# internal_env_board_new.net
KiCad netlist of a schematic drawn in EAGLE
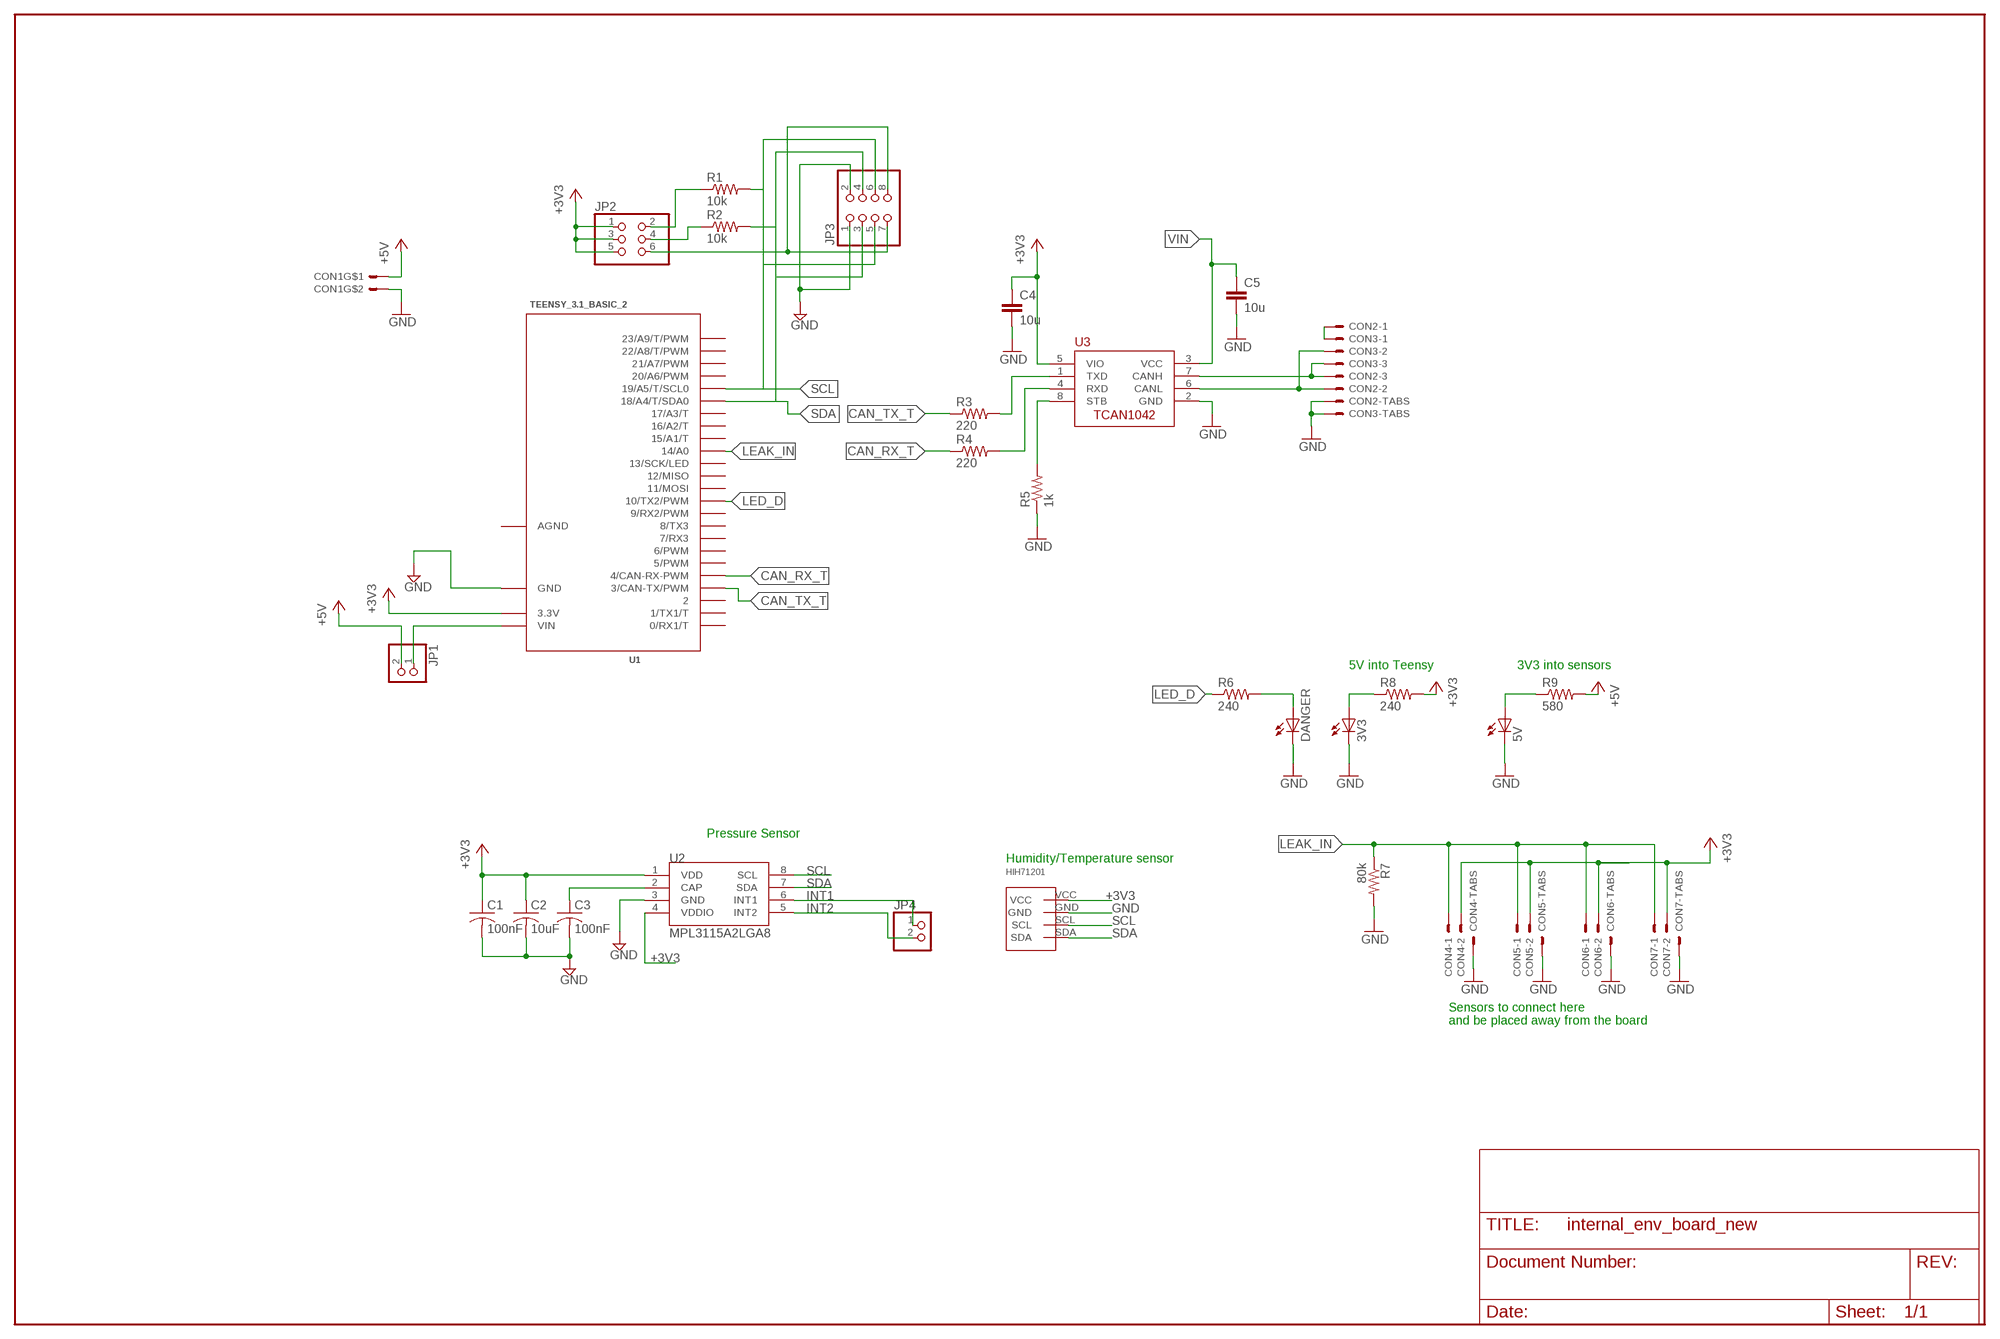
[diagram p0: schematic, sheet 1]

(export (version "E")
  (design (tool "Eeschema 10.0.6"))
  (components
    (comp (ref "3V3")
      (value "LEDSMT1206")
      (footprint "eagle-import:1206")
      (libsource (lib "eagle-import") (part "LEDSMT1206"))
    )
    (comp (ref "5V")
      (value "LEDSMT1206")
      (footprint "eagle-import:1206")
      (libsource (lib "eagle-import") (part "LEDSMT1206"))
    )
    (comp (ref "C1")
      (value "100nF")
      (footprint "eagle-import:C1206")
      (libsource (lib "eagle-import") (part "C-USC1206"))
    )
    (comp (ref "C2")
      (value "10uF")
      (footprint "eagle-import:C1206")
      (libsource (lib "eagle-import") (part "C-USC1206"))
    )
    (comp (ref "C3")
      (value "100nF")
      (footprint "eagle-import:C1206")
      (libsource (lib "eagle-import") (part "C-USC1206"))
    )
    (comp (ref "C4")
      (value "10u")
      (footprint "eagle-import:C0805")
      (libsource (lib "eagle-import") (part "C-EUC0805"))
    )
    (comp (ref "C5")
      (value "10u")
      (footprint "eagle-import:C0805")
      (libsource (lib "eagle-import") (part "C-EUC0805"))
    )
    (comp (ref "CON1")
      (value "MOLEX_5566-2")
      (footprint "eagle-import:5566-2")
      (libsource (lib "eagle-import") (part "MOLEX_5566-2"))
    )
    (comp (ref "CON2")
      (value "SM03B-GHS-TB")
      (footprint "eagle-import:SM03B-GHS-TB")
      (libsource (lib "eagle-import") (part "SM03B-GHS-TB"))
    )
    (comp (ref "CON3")
      (value "SM03B-GHS-TB")
      (footprint "eagle-import:SM03B-GHS-TB")
      (libsource (lib "eagle-import") (part "SM03B-GHS-TB"))
    )
    (comp (ref "CON4")
      (value "SM02B-GHS-TB")
      (footprint "eagle-import:SM02B-GHS-TB")
      (libsource (lib "eagle-import") (part "SM02B-GHS-TB"))
    )
    (comp (ref "CON5")
      (value "SM02B-GHS-TB")
      (footprint "eagle-import:SM02B-GHS-TB")
      (libsource (lib "eagle-import") (part "SM02B-GHS-TB"))
    )
    (comp (ref "CON6")
      (value "SM02B-GHS-TB")
      (footprint "eagle-import:SM02B-GHS-TB")
      (libsource (lib "eagle-import") (part "SM02B-GHS-TB"))
    )
    (comp (ref "CON7")
      (value "SM02B-GHS-TB")
      (footprint "eagle-import:SM02B-GHS-TB")
      (libsource (lib "eagle-import") (part "SM02B-GHS-TB"))
    )
    (comp (ref "DANGER")
      (value "LEDSMT1206")
      (footprint "eagle-import:1206")
      (libsource (lib "eagle-import") (part "LEDSMT1206"))
    )
    (comp (ref "HIH71201")
      (value "HIH7120")
      (footprint "eagle-import:SIP4")
      (libsource (lib "eagle-import") (part "HIH7120"))
    )
    (comp (ref "JP1")
      (value "PINHD-1X2")
      (footprint "eagle-import:1X02")
      (libsource (lib "eagle-import") (part "pinhead_325_PINHD-1X2"))
    )
    (comp (ref "JP2")
      (value "PINHD-2X3")
      (footprint "eagle-import:2X03")
      (libsource (lib "eagle-import") (part "PINHD-2X3"))
    )
    (comp (ref "JP3")
      (value "PINHD-2X4")
      (footprint "eagle-import:2X04")
      (libsource (lib "eagle-import") (part "PINHD-2X4"))
    )
    (comp (ref "JP4")
      (value "PINHD-1X2")
      (footprint "eagle-import:1X02")
      (libsource (lib "eagle-import") (part "PINHD-1X2"))
    )
    (comp (ref "R1")
      (value "10k")
      (footprint "eagle-import:R1206")
      (libsource (lib "eagle-import") (part "R-US_R1206"))
    )
    (comp (ref "R2")
      (value "10k")
      (footprint "eagle-import:R1206")
      (libsource (lib "eagle-import") (part "R-US_R1206"))
    )
    (comp (ref "R3")
      (value "220")
      (footprint "eagle-import:R0805")
      (libsource (lib "eagle-import") (part "R-US_R0805"))
    )
    (comp (ref "R4")
      (value "220")
      (footprint "eagle-import:R0805")
      (libsource (lib "eagle-import") (part "R-US_R0805"))
    )
    (comp (ref "R5")
      (value "1k")
      (footprint "eagle-import:R0805")
      (libsource (lib "eagle-import") (part "R-US_R0805"))
    )
    (comp (ref "R6")
      (value "240")
      (footprint "eagle-import:R1206")
      (libsource (lib "eagle-import") (part "resistor_348_R-US_R1206"))
    )
    (comp (ref "R7")
      (value "80k")
      (footprint "eagle-import:R1206")
      (libsource (lib "eagle-import") (part "resistor_348_R-US_R1206"))
    )
    (comp (ref "R8")
      (value "240")
      (footprint "eagle-import:R1206")
      (libsource (lib "eagle-import") (part "resistor_348_R-US_R1206"))
    )
    (comp (ref "R9")
      (value "580")
      (footprint "eagle-import:R1206")
      (libsource (lib "eagle-import") (part "resistor_348_R-US_R1206"))
    )
    (comp (ref "U1")
      (value "TEENSY_3.1_BASIC_2")
      (footprint "eagle-import:TEENSY_3.1_BASIC_2")
      (libsource (lib "eagle-import") (part "TEENSY_3.1_BASIC_2"))
    )
    (comp (ref "U2")
      (value "MPL3115A2LGA8")
      (footprint "eagle-import:LGA8")
      (libsource (lib "eagle-import") (part "MPL3115A2LGA8"))
    )
    (comp (ref "U3")
      (value "TCAN1042HVDR")
      (footprint "eagle-import:SO-8")
      (libsource (lib "eagle-import") (part "TCAN1042HVDR"))
    )
  )
  (nets
    (net (code "1") (name "+3V3") (class "Default")
      (node (ref "C1") (pin "1") (pinfunction "1_1") (pintype "passive"))
      (node (ref "C2") (pin "1") (pinfunction "1_1") (pintype "passive"))
      (node (ref "C4") (pin "1") (pinfunction "1_1") (pintype "passive"))
      (node (ref "CON4") (pin "P$2") (pinfunction "S_P$2") (pintype "passive"))
      (node (ref "CON5") (pin "P$2") (pinfunction "S_P$2") (pintype "passive"))
      (node (ref "CON6") (pin "P$2") (pinfunction "S_P$2") (pintype "passive"))
      (node (ref "CON7") (pin "P$2") (pinfunction "S_P$2") (pintype "passive"))
      (node (ref "HIH71201") (pin "VCC") (pinfunction "VCC_VCC") (pintype "power_in"))
      (node (ref "JP2") (pin "1") (pinfunction "1_1") (pintype "passive"))
      (node (ref "JP2") (pin "3") (pinfunction "3_3") (pintype "passive"))
      (node (ref "JP2") (pin "5") (pinfunction "5_5") (pintype "passive"))
      (node (ref "R8") (pin "2") (pinfunction "2_2") (pintype "passive"))
      (node (ref "U1") (pin "3.3V") (pinfunction "3.3V_3.3V") (pintype "power_in"))
      (node (ref "U2") (pin "1") (pinfunction "VDD_1") (pintype "bidirectional"))
      (node (ref "U2") (pin "4") (pinfunction "VDDIO_4") (pintype "bidirectional"))
      (node (ref "U3") (pin "5") (pinfunction "VIO_5") (pintype "bidirectional"))
    )
    (net (code "2") (name "+5V") (class "Default")
      (node (ref "CON1") (pin "1") (pinfunction "S_1") (pintype "passive"))
      (node (ref "JP1") (pin "2") (pinfunction "2_2") (pintype "passive"))
      (node (ref "R9") (pin "2") (pinfunction "2_2") (pintype "passive"))
    )
    (net (code "3") (name "/AGND") (class "Default")
      (node (ref "U1") (pin "AGND") (pinfunction "AGND_AGND") (pintype "power_in"))
    )
    (net (code "4") (name "/INT1") (class "Default")
      (node (ref "JP4") (pin "1") (pinfunction "1_1") (pintype "passive"))
      (node (ref "U2") (pin "6") (pinfunction "INT1_6") (pintype "bidirectional"))
    )
    (net (code "5") (name "/INT2") (class "Default")
      (node (ref "JP4") (pin "2") (pinfunction "2_2") (pintype "passive"))
      (node (ref "U2") (pin "5") (pinfunction "INT2_5") (pintype "bidirectional"))
    )
    (net (code "6") (name "CAN_RX_T") (class "Default")
      (node (ref "R4") (pin "1") (pinfunction "1_1") (pintype "passive"))
      (node (ref "U1") (pin "4") (pinfunction "4/CAN-RX-PWM_4") (pintype "bidirectional"))
    )
    (net (code "7") (name "CAN_TX_T") (class "Default")
      (node (ref "R3") (pin "1") (pinfunction "1_1") (pintype "passive"))
      (node (ref "U1") (pin "3") (pinfunction "3/CAN-TX/PWM_3") (pintype "bidirectional"))
    )
    (net (code "8") (name "GND") (class "Default")
      (node (ref "3V3") (pin "C") (pinfunction "C_C") (pintype "passive"))
      (node (ref "5V") (pin "C") (pinfunction "C_C") (pintype "passive"))
      (node (ref "C1") (pin "2") (pinfunction "2_2") (pintype "passive"))
      (node (ref "C2") (pin "2") (pinfunction "2_2") (pintype "passive"))
      (node (ref "C3") (pin "2") (pinfunction "2_2") (pintype "passive"))
      (node (ref "C4") (pin "2") (pinfunction "2_2") (pintype "passive"))
      (node (ref "C5") (pin "2") (pinfunction "2_2") (pintype "passive"))
      (node (ref "CON1") (pin "2") (pinfunction "S_2") (pintype "passive"))
      (node (ref "CON2") (pin "P$4") (pinfunction "S_P$4") (pintype "passive"))
      (node (ref "CON2") (pin "P$5") (pinfunction "S_P$5") (pintype "passive"))
      (node (ref "CON3") (pin "P$4") (pinfunction "S_P$4") (pintype "passive"))
      (node (ref "CON3") (pin "P$5") (pinfunction "S_P$5") (pintype "passive"))
      (node (ref "CON4") (pin "P$3") (pinfunction "S_P$3") (pintype "passive"))
      (node (ref "CON4") (pin "P$4") (pinfunction "S_P$4") (pintype "passive"))
      (node (ref "CON5") (pin "P$3") (pinfunction "S_P$3") (pintype "passive"))
      (node (ref "CON5") (pin "P$4") (pinfunction "S_P$4") (pintype "passive"))
      (node (ref "CON6") (pin "P$3") (pinfunction "S_P$3") (pintype "passive"))
      (node (ref "CON6") (pin "P$4") (pinfunction "S_P$4") (pintype "passive"))
      (node (ref "CON7") (pin "P$3") (pinfunction "S_P$3") (pintype "passive"))
      (node (ref "CON7") (pin "P$4") (pinfunction "S_P$4") (pintype "passive"))
      (node (ref "DANGER") (pin "C") (pinfunction "C_C") (pintype "passive"))
      (node (ref "HIH71201") (pin "GND") (pinfunction "GND_GND") (pintype "power_in"))
      (node (ref "JP3") (pin "1") (pinfunction "1_1") (pintype "passive"))
      (node (ref "JP3") (pin "2") (pinfunction "2_2") (pintype "passive"))
      (node (ref "R5") (pin "1") (pinfunction "1_1") (pintype "passive"))
      (node (ref "R7") (pin "2") (pinfunction "2_2") (pintype "passive"))
      (node (ref "U1") (pin "GND") (pinfunction "GND_GND") (pintype "power_in"))
      (node (ref "U2") (pin "3") (pinfunction "GND_3") (pintype "bidirectional"))
      (node (ref "U3") (pin "2") (pinfunction "GND_2") (pintype "bidirectional"))
    )
    (net (code "9") (name "LEAK_IN") (class "Default")
      (node (ref "CON4") (pin "P$1") (pinfunction "S_P$1") (pintype "passive"))
      (node (ref "CON5") (pin "P$1") (pinfunction "S_P$1") (pintype "passive"))
      (node (ref "CON6") (pin "P$1") (pinfunction "S_P$1") (pintype "passive"))
      (node (ref "CON7") (pin "P$1") (pinfunction "S_P$1") (pintype "passive"))
      (node (ref "R7") (pin "1") (pinfunction "1_1") (pintype "passive"))
      (node (ref "U1") (pin "14/A0") (pinfunction "14/A0_14/A0") (pintype "bidirectional"))
    )
    (net (code "10") (name "LED_D") (class "Default")
      (node (ref "R6") (pin "1") (pinfunction "1_1") (pintype "passive"))
      (node (ref "U1") (pin "10") (pinfunction "10/TX2/PWM_10") (pintype "bidirectional"))
    )
    (net (code "11") (name "Net-(3V3-PadA)") (class "Default")
      (node (ref "3V3") (pin "A") (pinfunction "A_A") (pintype "passive"))
      (node (ref "R8") (pin "1") (pinfunction "1_1") (pintype "passive"))
    )
    (net (code "12") (name "Net-(5V-PadA)") (class "Default")
      (node (ref "5V") (pin "A") (pinfunction "A_A") (pintype "passive"))
      (node (ref "R9") (pin "1") (pinfunction "1_1") (pintype "passive"))
    )
    (net (code "13") (name "Net-(CON2A-S)") (class "Default")
      (node (ref "CON2") (pin "P$1") (pinfunction "S_P$1") (pintype "passive"))
      (node (ref "CON3") (pin "P$1") (pinfunction "S_P$1") (pintype "passive"))
    )
    (net (code "14") (name "Net-(CON2B-S)") (class "Default")
      (node (ref "CON2") (pin "P$2") (pinfunction "S_P$2") (pintype "passive"))
      (node (ref "CON3") (pin "P$2") (pinfunction "S_P$2") (pintype "passive"))
      (node (ref "U3") (pin "6") (pinfunction "CANL_6") (pintype "bidirectional"))
    )
    (net (code "15") (name "Net-(CON2C-S)") (class "Default")
      (node (ref "CON2") (pin "P$3") (pinfunction "S_P$3") (pintype "passive"))
      (node (ref "CON3") (pin "P$3") (pinfunction "S_P$3") (pintype "passive"))
      (node (ref "U3") (pin "7") (pinfunction "CANH_7") (pintype "bidirectional"))
    )
    (net (code "16") (name "Net-(DANGER-PadA)") (class "Default")
      (node (ref "DANGER") (pin "A") (pinfunction "A_A") (pintype "passive"))
      (node (ref "R6") (pin "2") (pinfunction "2_2") (pintype "passive"))
    )
    (net (code "17") (name "Net-(JP2-Pad2)") (class "Default")
      (node (ref "JP2") (pin "2") (pinfunction "2_2") (pintype "passive"))
      (node (ref "R1") (pin "1") (pinfunction "1_1") (pintype "passive"))
    )
    (net (code "18") (name "Net-(JP2-Pad4)") (class "Default")
      (node (ref "JP2") (pin "4") (pinfunction "4_4") (pintype "passive"))
      (node (ref "R2") (pin "1") (pinfunction "1_1") (pintype "passive"))
    )
    (net (code "19") (name "Net-(JP2-Pad6)") (class "Default")
      (node (ref "JP2") (pin "6") (pinfunction "6_6") (pintype "passive"))
      (node (ref "JP3") (pin "7") (pinfunction "7_7") (pintype "passive"))
      (node (ref "JP3") (pin "8") (pinfunction "8_8") (pintype "passive"))
    )
    (net (code "20") (name "Net-(U2-CAP)") (class "Default")
      (node (ref "C3") (pin "1") (pinfunction "1_1") (pintype "passive"))
      (node (ref "U2") (pin "2") (pinfunction "CAP_2") (pintype "bidirectional"))
    )
    (net (code "21") (name "Net-(U3-RXD)") (class "Default")
      (node (ref "R4") (pin "2") (pinfunction "2_2") (pintype "passive"))
      (node (ref "U3") (pin "4") (pinfunction "RXD_4") (pintype "bidirectional"))
    )
    (net (code "22") (name "Net-(U3-STB)") (class "Default")
      (node (ref "R5") (pin "2") (pinfunction "2_2") (pintype "passive"))
      (node (ref "U3") (pin "8") (pinfunction "STB_8") (pintype "bidirectional"))
    )
    (net (code "23") (name "Net-(U3-TXD)") (class "Default")
      (node (ref "R3") (pin "2") (pinfunction "2_2") (pintype "passive"))
      (node (ref "U3") (pin "1") (pinfunction "TXD_1") (pintype "bidirectional"))
    )
    (net (code "24") (name "SCL") (class "Default")
      (node (ref "HIH71201") (pin "SCL") (pinfunction "SCL_SCL") (pintype "bidirectional"))
      (node (ref "JP3") (pin "5") (pinfunction "5_5") (pintype "passive"))
      (node (ref "JP3") (pin "6") (pinfunction "6_6") (pintype "passive"))
      (node (ref "R1") (pin "2") (pinfunction "2_2") (pintype "passive"))
      (node (ref "U1") (pin "19/A5") (pinfunction "19/A5/T/SCL0_19/A5") (pintype "bidirectional"))
      (node (ref "U2") (pin "8") (pinfunction "SCL_8") (pintype "bidirectional"))
    )
    (net (code "25") (name "SDA") (class "Default")
      (node (ref "HIH71201") (pin "SDA") (pinfunction "SDA_SDA") (pintype "bidirectional"))
      (node (ref "JP3") (pin "3") (pinfunction "3_3") (pintype "passive"))
      (node (ref "JP3") (pin "4") (pinfunction "4_4") (pintype "passive"))
      (node (ref "R2") (pin "2") (pinfunction "2_2") (pintype "passive"))
      (node (ref "U1") (pin "18/A4") (pinfunction "18/A4/T/SDA0_18/A4") (pintype "bidirectional"))
      (node (ref "U2") (pin "7") (pinfunction "SDA_7") (pintype "bidirectional"))
    )
    (net (code "26") (name "VIN") (class "Default")
      (node (ref "C5") (pin "1") (pinfunction "1_1") (pintype "passive"))
      (node (ref "JP1") (pin "1") (pinfunction "1_1") (pintype "passive"))
      (node (ref "U1") (pin "VIN") (pinfunction "VIN_VIN") (pintype "power_in"))
      (node (ref "U3") (pin "3") (pinfunction "VCC_3") (pintype "bidirectional"))
    )
    (net (code "27") (name "unconnected-(U1-0{slash}RX1{slash}T-Pad0)") (class "Default")
      (node (ref "U1") (pin "0") (pinfunction "0/RX1/T_0") (pintype "bidirectional"))
    )
    (net (code "28") (name "unconnected-(U1-1{slash}TX1{slash}T-Pad1)") (class "Default")
      (node (ref "U1") (pin "1") (pinfunction "1/TX1/T_1") (pintype "bidirectional"))
    )
    (net (code "29") (name "unconnected-(U1-5{slash}PWM-Pad5)") (class "Default")
      (node (ref "U1") (pin "5") (pinfunction "5/PWM_5") (pintype "bidirectional"))
    )
    (net (code "30") (name "unconnected-(U1-6{slash}PWM-Pad6)") (class "Default")
      (node (ref "U1") (pin "6") (pinfunction "6/PWM_6") (pintype "bidirectional"))
    )
    (net (code "31") (name "unconnected-(U1-7{slash}RX3-Pad7)") (class "Default")
      (node (ref "U1") (pin "7") (pinfunction "7/RX3_7") (pintype "bidirectional"))
    )
    (net (code "32") (name "unconnected-(U1-8{slash}TX3-Pad8)") (class "Default")
      (node (ref "U1") (pin "8") (pinfunction "8/TX3_8") (pintype "bidirectional"))
    )
    (net (code "33") (name "unconnected-(U1-9{slash}RX2{slash}PWM-Pad9)") (class "Default")
      (node (ref "U1") (pin "9") (pinfunction "9/RX2/PWM_9") (pintype "bidirectional"))
    )
    (net (code "34") (name "unconnected-(U1-11{slash}MOSI-Pad11)") (class "Default")
      (node (ref "U1") (pin "11") (pinfunction "11/MOSI_11") (pintype "bidirectional"))
    )
    (net (code "35") (name "unconnected-(U1-12{slash}MISO-Pad12)") (class "Default")
      (node (ref "U1") (pin "12") (pinfunction "12/MISO_12") (pintype "bidirectional"))
    )
    (net (code "36") (name "unconnected-(U1-13{slash}SCK{slash}LED-Pad13)") (class "Default")
      (node (ref "U1") (pin "13") (pinfunction "13/SCK/LED_13") (pintype "bidirectional"))
    )
    (net (code "37") (name "unconnected-(U1-15{slash}A1{slash}T-Pad15{slash}A1)") (class "Default")
      (node (ref "U1") (pin "15/A1") (pinfunction "15/A1/T_15/A1") (pintype "bidirectional"))
    )
    (net (code "38") (name "unconnected-(U1-16{slash}A2{slash}T-Pad16{slash}A2)") (class "Default")
      (node (ref "U1") (pin "16/A2") (pinfunction "16/A2/T_16/A2") (pintype "bidirectional"))
    )
    (net (code "39") (name "unconnected-(U1-17{slash}A3{slash}T-Pad17{slash}A3)") (class "Default")
      (node (ref "U1") (pin "17/A3") (pinfunction "17/A3/T_17/A3") (pintype "bidirectional"))
    )
    (net (code "40") (name "unconnected-(U1-20{slash}A6{slash}PWM-Pad20{slash}A6)") (class "Default")
      (node (ref "U1") (pin "20/A6") (pinfunction "20/A6/PWM_20/A6") (pintype "bidirectional"))
    )
    (net (code "41") (name "unconnected-(U1-21{slash}A7{slash}PWM-Pad21{slash}A7)") (class "Default")
      (node (ref "U1") (pin "21/A7") (pinfunction "21/A7/PWM_21/A7") (pintype "bidirectional"))
    )
    (net (code "42") (name "unconnected-(U1-22{slash}A8{slash}T{slash}PWM-Pad22{slash}A8)") (class "Default")
      (node (ref "U1") (pin "22/A8") (pinfunction "22/A8/T/PWM_22/A8") (pintype "bidirectional"))
    )
    (net (code "43") (name "unconnected-(U1-23{slash}A9{slash}T{slash}PWM-Pad23{slash}A9)") (class "Default")
      (node (ref "U1") (pin "23/A9") (pinfunction "23/A9/T/PWM_23/A9") (pintype "bidirectional"))
    )
    (net (code "44") (name "unconnected-(U1-Pad2)") (class "Default")
      (node (ref "U1") (pin "2") (pinfunction "2_2") (pintype "bidirectional"))
    )
  )
)
